# T_STorM32_motor_v25E-jst.net
KiCad netlist of a schematic drawn in EAGLE
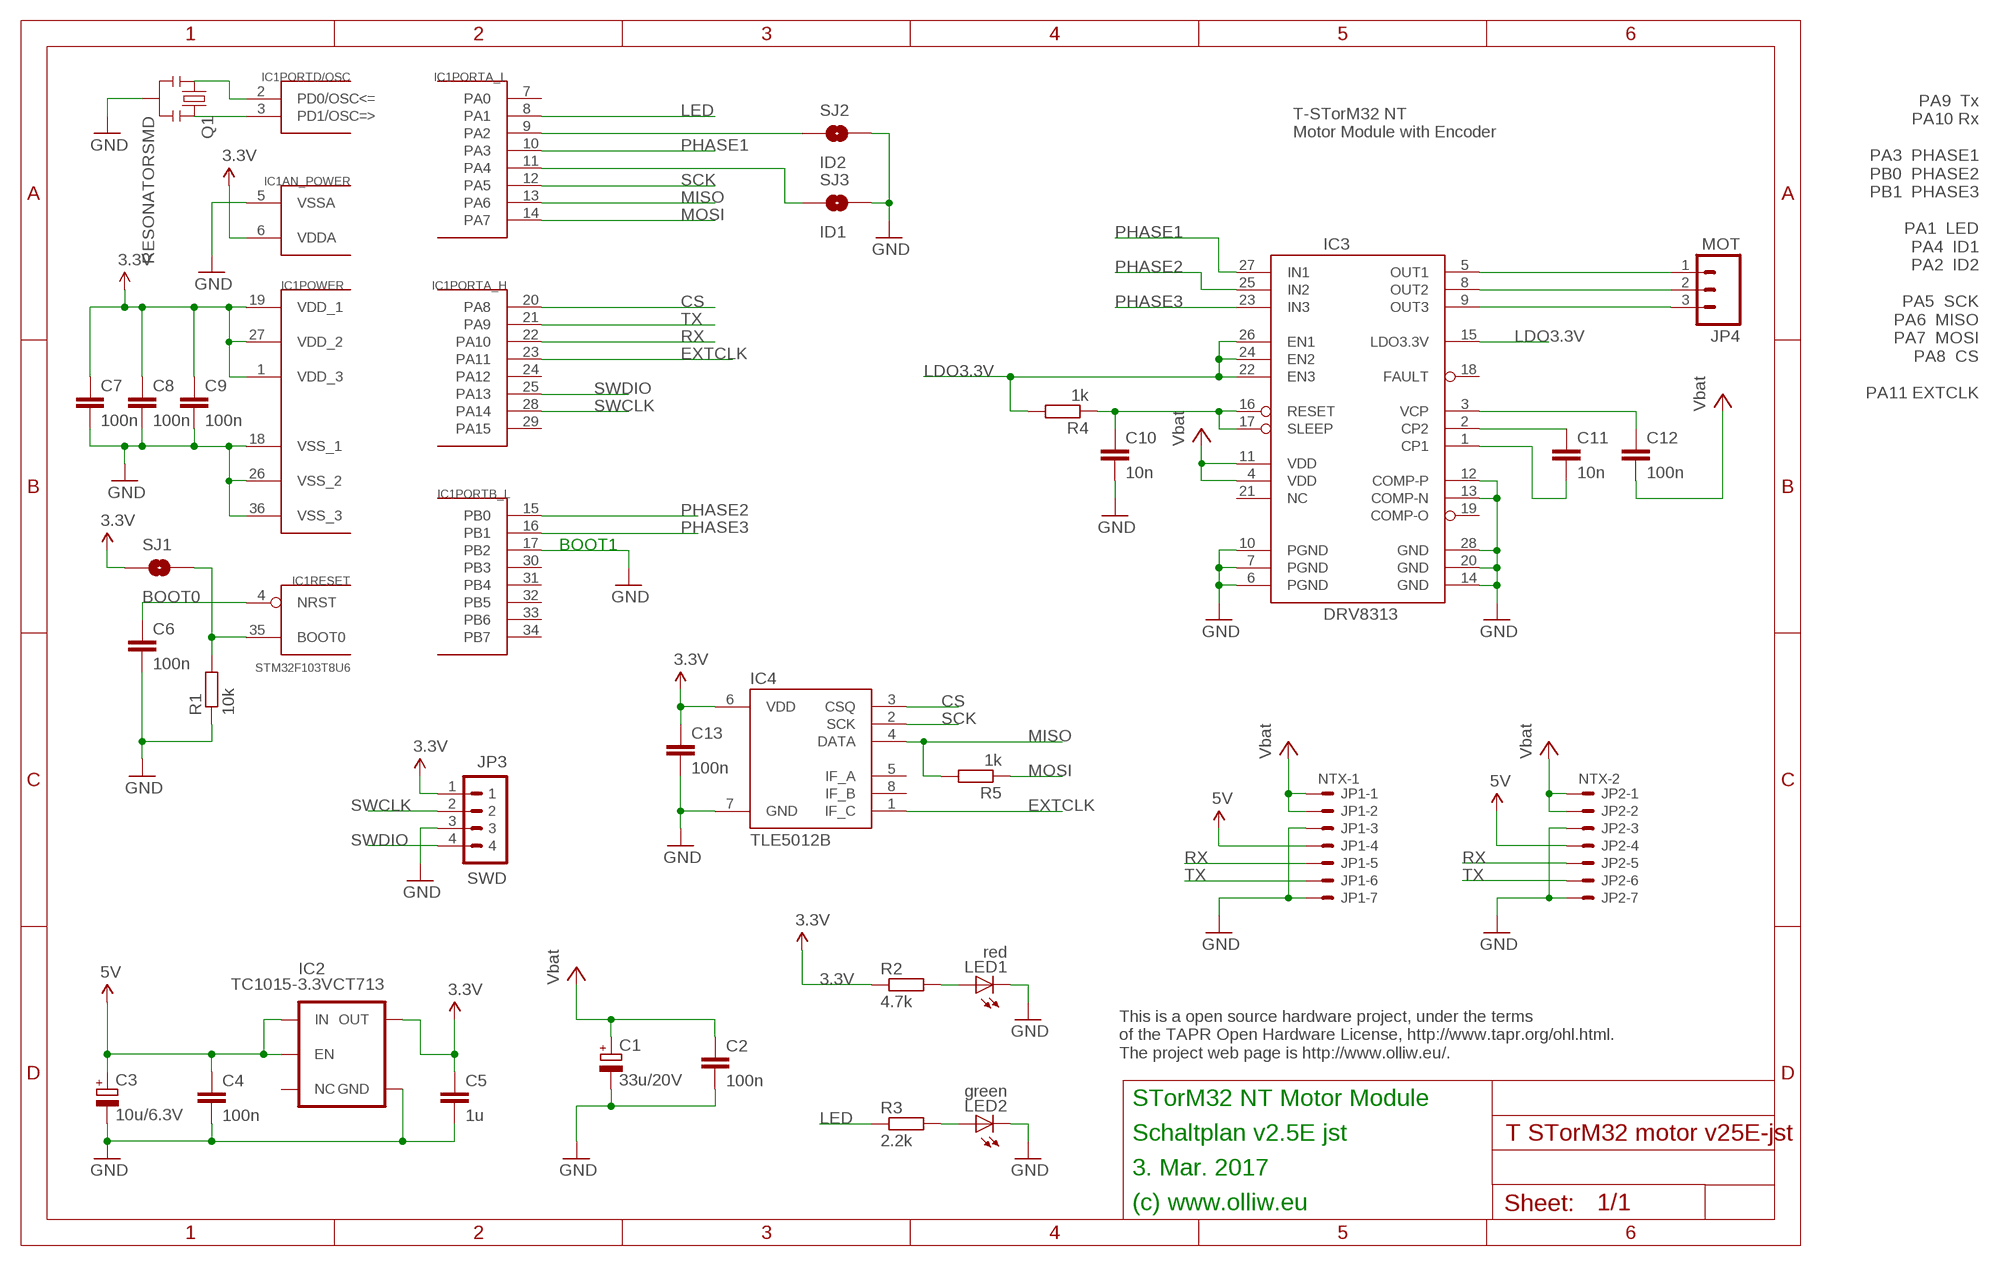
[diagram p0: schematic, sheet 1]

(export (version "E")
  (design (tool "Eeschema 10.0.6"))
  (components
    (comp (ref "C1")
      (value "33u/20V")
      (footprint "eagle-import:SMC_C")
      (libsource (lib "eagle-import") (part "CPOL-EUSMCC"))
    )
    (comp (ref "C2")
      (value "100n")
      (footprint "eagle-import:C0603")
      (libsource (lib "eagle-import") (part "C-EUC0603"))
    )
    (comp (ref "C3")
      (value "10u/6.3V")
      (footprint "eagle-import:SMC_B")
      (libsource (lib "eagle-import") (part "CPOL-EUSMCB"))
    )
    (comp (ref "C4")
      (value "100n")
      (footprint "eagle-import:C0603")
      (libsource (lib "eagle-import") (part "C-EUC0603"))
    )
    (comp (ref "C5")
      (value "1u")
      (footprint "eagle-import:C0603")
      (libsource (lib "eagle-import") (part "C-EUC0603"))
    )
    (comp (ref "C6")
      (value "100n")
      (footprint "eagle-import:C0603")
      (libsource (lib "eagle-import") (part "C-EUC0603"))
    )
    (comp (ref "C7")
      (value "100n")
      (footprint "eagle-import:C0603")
      (libsource (lib "eagle-import") (part "C-EUC0603"))
    )
    (comp (ref "C8")
      (value "100n")
      (footprint "eagle-import:C0603")
      (libsource (lib "eagle-import") (part "C-EUC0603"))
    )
    (comp (ref "C9")
      (value "100n")
      (footprint "eagle-import:C0603")
      (libsource (lib "eagle-import") (part "C-EUC0603"))
    )
    (comp (ref "C10")
      (value "10n")
      (footprint "eagle-import:C0603")
      (libsource (lib "eagle-import") (part "C-EUC0603"))
    )
    (comp (ref "C11")
      (value "10n")
      (footprint "eagle-import:C0603")
      (libsource (lib "eagle-import") (part "C-EUC0603"))
    )
    (comp (ref "C12")
      (value "100n")
      (footprint "eagle-import:C0603")
      (libsource (lib "eagle-import") (part "C-EUC0603"))
    )
    (comp (ref "C13")
      (value "100n")
      (footprint "eagle-import:C0603")
      (libsource (lib "eagle-import") (part "C-EUC0603"))
    )
    (comp (ref "IC1")
      (value "STM32F103T8U6")
      (footprint "eagle-import:VFQFPN36")
      (libsource (lib "eagle-import") (part "STM32F10XTXU6"))
    )
    (comp (ref "IC2")
      (value "TC1015-3.3VCT713")
      (footprint "eagle-import:SOT23-5")
      (libsource (lib "eagle-import") (part "V_REG_TPS76433SOT23-5"))
    )
    (comp (ref "IC3")
      (value "DRV8313")
      (footprint "eagle-import:HTSSOP28")
      (libsource (lib "eagle-import") (part "DRV8313"))
    )
    (comp (ref "IC4")
      (value "TLE5012B")
      (footprint "eagle-import:SO08")
      (libsource (lib "eagle-import") (part "TLE5012B"))
    )
    (comp (ref "JP1")
      (value "NTX-1")
      (footprint "eagle-import:SM07B-SRSS-TB")
      (libsource (lib "eagle-import") (part "?M07B-SRSS-TBS"))
    )
    (comp (ref "JP2")
      (value "NTX-2")
      (footprint "eagle-import:SM07B-SRSS-TB")
      (libsource (lib "eagle-import") (part "?M07B-SRSS-TBS"))
    )
    (comp (ref "JP3")
      (value "SWD")
      (footprint "eagle-import:4X1_1P27_OCT_BILEX")
      (libsource (lib "eagle-import") (part "P4X1_1P27-OCT_BILEX"))
    )
    (comp (ref "JP4")
      (value "MOT")
      (footprint "eagle-import:1X03")
      (libsource (lib "eagle-import") (part "M03PTH"))
    )
    (comp (ref "LED1")
      (value "red")
      (footprint "eagle-import:CHIPLED_0603")
      (libsource (lib "eagle-import") (part "LEDCHIPLED_0603"))
    )
    (comp (ref "LED2")
      (value "green")
      (footprint "eagle-import:CHIPLED_0603")
      (libsource (lib "eagle-import") (part "LEDCHIPLED_0603"))
    )
    (comp (ref "Q1")
      (value "RESONATORSMD")
      (footprint "eagle-import:RESONATOR-SMD")
      (libsource (lib "eagle-import") (part "RESONATORSMD"))
    )
    (comp (ref "R1")
      (value "10k")
      (footprint "eagle-import:R0603")
      (libsource (lib "eagle-import") (part "R-EU_R0603"))
    )
    (comp (ref "R2")
      (value "4.7k")
      (footprint "eagle-import:R0603")
      (libsource (lib "eagle-import") (part "R-EU_R0603"))
    )
    (comp (ref "R3")
      (value "2.2k")
      (footprint "eagle-import:R0603")
      (libsource (lib "eagle-import") (part "R-EU_R0603"))
    )
    (comp (ref "R4")
      (value "1k")
      (footprint "eagle-import:R0603")
      (libsource (lib "eagle-import") (part "R-EU_R0603"))
    )
    (comp (ref "R5")
      (value "1k")
      (footprint "eagle-import:R0603")
      (libsource (lib "eagle-import") (part "R-EU_R0603"))
    )
    (comp (ref "SJ1")
      (value "BOOT0")
      (footprint "eagle-import:SJ_2S-NO")
      (libsource (lib "eagle-import") (part "SOLDERJUMPERNO"))
    )
    (comp (ref "SJ2")
      (value "ID2")
      (footprint "eagle-import:SJ_2S-NO")
      (libsource (lib "eagle-import") (part "SOLDERJUMPERNO"))
    )
    (comp (ref "SJ3")
      (value "ID1")
      (footprint "eagle-import:SJ_2S-NO")
      (libsource (lib "eagle-import") (part "SOLDERJUMPERNO"))
    )
  )
  (nets
    (net (code "1") (name "/CS") (class "Default")
      (node (ref "IC1") (pin "20") (pinfunction "PA8_20") (pintype "bidirectional"))
      (node (ref "IC4") (pin "3") (pinfunction "CSQ_3") (pintype "input"))
    )
    (net (code "2") (name "/EXTCLK") (class "Default")
      (node (ref "IC1") (pin "23") (pinfunction "PA11_23") (pintype "bidirectional"))
      (node (ref "IC4") (pin "1") (pinfunction "IF_C_1") (pintype "bidirectional"))
    )
    (net (code "3") (name "/LDO3.3V") (class "Default")
      (node (ref "IC3") (pin "15") (pinfunction "LDO3.3V_15") (pintype "output"))
      (node (ref "IC3") (pin "22") (pinfunction "EN3_22") (pintype "input"))
      (node (ref "IC3") (pin "24") (pinfunction "EN2_24") (pintype "input"))
      (node (ref "IC3") (pin "26") (pinfunction "EN1_26") (pintype "input"))
      (node (ref "R4") (pin "2") (pinfunction "2_2") (pintype "passive"))
    )
    (net (code "4") (name "/LED") (class "Default")
      (node (ref "IC1") (pin "8") (pinfunction "PA1_8") (pintype "bidirectional"))
      (node (ref "R3") (pin "1") (pinfunction "1_1") (pintype "passive"))
    )
    (net (code "5") (name "/MISO") (class "Default")
      (node (ref "IC1") (pin "13") (pinfunction "PA6_13") (pintype "bidirectional"))
      (node (ref "IC4") (pin "4") (pinfunction "DATA_4") (pintype "bidirectional"))
      (node (ref "R5") (pin "2") (pinfunction "2_2") (pintype "passive"))
    )
    (net (code "6") (name "/MOSI") (class "Default")
      (node (ref "IC1") (pin "14") (pinfunction "PA7_14") (pintype "bidirectional"))
      (node (ref "R5") (pin "1") (pinfunction "1_1") (pintype "passive"))
    )
    (net (code "7") (name "/PHASE1") (class "Default")
      (node (ref "IC1") (pin "10") (pinfunction "PA3_10") (pintype "bidirectional"))
      (node (ref "IC3") (pin "27") (pinfunction "IN1_27") (pintype "input"))
    )
    (net (code "8") (name "/PHASE2") (class "Default")
      (node (ref "IC1") (pin "15") (pinfunction "PB0_15") (pintype "bidirectional"))
      (node (ref "IC3") (pin "25") (pinfunction "IN2_25") (pintype "input"))
    )
    (net (code "9") (name "/PHASE3") (class "Default")
      (node (ref "IC1") (pin "16") (pinfunction "PB1_16") (pintype "bidirectional"))
      (node (ref "IC3") (pin "23") (pinfunction "IN3_23") (pintype "input"))
    )
    (net (code "10") (name "/RX") (class "Default")
      (node (ref "IC1") (pin "22") (pinfunction "PA10_22") (pintype "bidirectional"))
      (node (ref "JP1") (pin "5") (pinfunction "S_5") (pintype "passive"))
      (node (ref "JP2") (pin "5") (pinfunction "S_5") (pintype "passive"))
    )
    (net (code "11") (name "/SCK") (class "Default")
      (node (ref "IC1") (pin "12") (pinfunction "PA5_12") (pintype "bidirectional"))
      (node (ref "IC4") (pin "2") (pinfunction "SCK_2") (pintype "input"))
    )
    (net (code "12") (name "/SWCLK") (class "Default")
      (node (ref "IC1") (pin "28") (pinfunction "PA14_28") (pintype "bidirectional"))
      (node (ref "JP3") (pin "2") (pinfunction "2_2") (pintype "passive"))
    )
    (net (code "13") (name "/SWDIO") (class "Default")
      (node (ref "IC1") (pin "25") (pinfunction "PA13_25") (pintype "bidirectional"))
      (node (ref "JP3") (pin "4") (pinfunction "4_4") (pintype "passive"))
    )
    (net (code "14") (name "/TX") (class "Default")
      (node (ref "IC1") (pin "21") (pinfunction "PA9_21") (pintype "bidirectional"))
      (node (ref "JP1") (pin "6") (pinfunction "S_6") (pintype "passive"))
      (node (ref "JP2") (pin "6") (pinfunction "S_6") (pintype "passive"))
    )
    (net (code "15") (name "3.3V") (class "Default")
      (node (ref "C13") (pin "1") (pinfunction "1_1") (pintype "passive"))
      (node (ref "C5") (pin "1") (pinfunction "1_1") (pintype "passive"))
      (node (ref "C7") (pin "1") (pinfunction "1_1") (pintype "passive"))
      (node (ref "C8") (pin "1") (pinfunction "1_1") (pintype "passive"))
      (node (ref "C9") (pin "1") (pinfunction "1_1") (pintype "passive"))
      (node (ref "IC1") (pin "1") (pinfunction "VDD_3_1") (pintype "power_in"))
      (node (ref "IC1") (pin "19") (pinfunction "VDD_1_19") (pintype "power_in"))
      (node (ref "IC1") (pin "27") (pinfunction "VDD_2_27") (pintype "power_in"))
      (node (ref "IC1") (pin "6") (pinfunction "VDDA_6") (pintype "power_in"))
      (node (ref "IC2") (pin "5") (pinfunction "OUT_5") (pintype "passive"))
      (node (ref "IC4") (pin "6") (pinfunction "VDD_6") (pintype "power_in"))
      (node (ref "JP3") (pin "1") (pinfunction "1_1") (pintype "passive"))
      (node (ref "R2") (pin "1") (pinfunction "1_1") (pintype "passive"))
      (node (ref "SJ1") (pin "1") (pinfunction "1_1") (pintype "passive"))
    )
    (net (code "16") (name "5V") (class "Default")
      (node (ref "C3") (pin "+") (pinfunction "+_+") (pintype "passive"))
      (node (ref "C4") (pin "1") (pinfunction "1_1") (pintype "passive"))
      (node (ref "IC2") (pin "1") (pinfunction "IN_1") (pintype "input"))
      (node (ref "IC2") (pin "3") (pinfunction "EN_3") (pintype "input"))
      (node (ref "JP1") (pin "4") (pinfunction "S_4") (pintype "passive"))
      (node (ref "JP2") (pin "4") (pinfunction "S_4") (pintype "passive"))
    )
    (net (code "17") (name "GND") (class "Default")
      (node (ref "C1") (pin "-") (pinfunction "-_-") (pintype "passive"))
      (node (ref "C10") (pin "2") (pinfunction "2_2") (pintype "passive"))
      (node (ref "C13") (pin "2") (pinfunction "2_2") (pintype "passive"))
      (node (ref "C2") (pin "2") (pinfunction "2_2") (pintype "passive"))
      (node (ref "C3") (pin "-") (pinfunction "-_-") (pintype "passive"))
      (node (ref "C4") (pin "2") (pinfunction "2_2") (pintype "passive"))
      (node (ref "C5") (pin "2") (pinfunction "2_2") (pintype "passive"))
      (node (ref "C6") (pin "2") (pinfunction "2_2") (pintype "passive"))
      (node (ref "C7") (pin "2") (pinfunction "2_2") (pintype "passive"))
      (node (ref "C8") (pin "2") (pinfunction "2_2") (pintype "passive"))
      (node (ref "C9") (pin "2") (pinfunction "2_2") (pintype "passive"))
      (node (ref "IC1") (pin "17") (pinfunction "PB2_17") (pintype "bidirectional"))
      (node (ref "IC1") (pin "18") (pinfunction "VSS_1_18") (pintype "power_in"))
      (node (ref "IC1") (pin "26") (pinfunction "VSS_2_26") (pintype "power_in"))
      (node (ref "IC1") (pin "36") (pinfunction "VSS_3_36") (pintype "power_in"))
      (node (ref "IC1") (pin "5") (pinfunction "VSSA_5") (pintype "power_in"))
      (node (ref "IC2") (pin "2") (pinfunction "GND_2") (pintype "input"))
      (node (ref "IC3") (pin "10") (pinfunction "PGND_10") (pintype "power_in"))
      (node (ref "IC3") (pin "12") (pinfunction "COMP-P_12") (pintype "input"))
      (node (ref "IC3") (pin "13") (pinfunction "COMP-N_13") (pintype "input"))
      (node (ref "IC3") (pin "14") (pinfunction "GND_14") (pintype "power_in"))
      (node (ref "IC3") (pin "20") (pinfunction "GND_20") (pintype "power_in"))
      (node (ref "IC3") (pin "28") (pinfunction "GND_28") (pintype "power_in"))
      (node (ref "IC3") (pin "6") (pinfunction "PGND_6") (pintype "power_in"))
      (node (ref "IC3") (pin "7") (pinfunction "PGND_7") (pintype "power_in"))
      (node (ref "IC4") (pin "7") (pinfunction "GND_7") (pintype "power_in"))
      (node (ref "JP1") (pin "3") (pinfunction "S_3") (pintype "passive"))
      (node (ref "JP1") (pin "7") (pinfunction "S_7") (pintype "passive"))
      (node (ref "JP2") (pin "3") (pinfunction "S_3") (pintype "passive"))
      (node (ref "JP2") (pin "7") (pinfunction "S_7") (pintype "passive"))
      (node (ref "JP3") (pin "3") (pinfunction "3_3") (pintype "passive"))
      (node (ref "LED1") (pin "C") (pinfunction "C_C") (pintype "passive"))
      (node (ref "LED2") (pin "C") (pinfunction "C_C") (pintype "passive"))
      (node (ref "Q1") (pin "2") (pinfunction "2_2") (pintype "passive"))
      (node (ref "R1") (pin "1") (pinfunction "1_1") (pintype "passive"))
      (node (ref "SJ2") (pin "2") (pinfunction "2_2") (pintype "passive"))
      (node (ref "SJ3") (pin "2") (pinfunction "2_2") (pintype "passive"))
    )
    (net (code "18") (name "Net-(IC1C-PA2)") (class "Default")
      (node (ref "IC1") (pin "9") (pinfunction "PA2_9") (pintype "bidirectional"))
      (node (ref "SJ2") (pin "1") (pinfunction "1_1") (pintype "passive"))
    )
    (net (code "19") (name "Net-(IC1C-PA4)") (class "Default")
      (node (ref "IC1") (pin "11") (pinfunction "PA4_11") (pintype "bidirectional"))
      (node (ref "SJ3") (pin "1") (pinfunction "1_1") (pintype "passive"))
    )
    (net (code "20") (name "Net-(IC1E-PD0{slash}OSC<=)") (class "Default")
      (node (ref "IC1") (pin "2") (pinfunction "PD0/OSC<=_2") (pintype "bidirectional"))
      (node (ref "Q1") (pin "1") (pinfunction "1_1") (pintype "passive"))
    )
    (net (code "21") (name "Net-(IC1E-PD1{slash}OSC=>)") (class "Default")
      (node (ref "IC1") (pin "3") (pinfunction "PD1/OSC=>_3") (pintype "bidirectional"))
      (node (ref "Q1") (pin "3") (pinfunction "3_3") (pintype "passive"))
    )
    (net (code "22") (name "Net-(IC1G-BOOT0)") (class "Default")
      (node (ref "IC1") (pin "35") (pinfunction "BOOT0_35") (pintype "input"))
      (node (ref "R1") (pin "2") (pinfunction "2_2") (pintype "passive"))
      (node (ref "SJ1") (pin "2") (pinfunction "2_2") (pintype "passive"))
    )
    (net (code "23") (name "Net-(IC1G-NRST)") (class "Default")
      (node (ref "C6") (pin "1") (pinfunction "1_1") (pintype "passive"))
      (node (ref "IC1") (pin "4") (pinfunction "NRST_4") (pintype "input"))
    )
    (net (code "24") (name "Net-(IC3-CP1)") (class "Default")
      (node (ref "C11") (pin "2") (pinfunction "2_2") (pintype "passive"))
      (node (ref "IC3") (pin "1") (pinfunction "CP1_1") (pintype "bidirectional"))
    )
    (net (code "25") (name "Net-(IC3-CP2)") (class "Default")
      (node (ref "C11") (pin "1") (pinfunction "1_1") (pintype "passive"))
      (node (ref "IC3") (pin "2") (pinfunction "CP2_2") (pintype "bidirectional"))
    )
    (net (code "26") (name "Net-(IC3-OUT1)") (class "Default")
      (node (ref "IC3") (pin "5") (pinfunction "OUT1_5") (pintype "output"))
      (node (ref "JP4") (pin "1") (pinfunction "1_1") (pintype "passive"))
    )
    (net (code "27") (name "Net-(IC3-OUT2)") (class "Default")
      (node (ref "IC3") (pin "8") (pinfunction "OUT2_8") (pintype "output"))
      (node (ref "JP4") (pin "2") (pinfunction "2_2") (pintype "passive"))
    )
    (net (code "28") (name "Net-(IC3-OUT3)") (class "Default")
      (node (ref "IC3") (pin "9") (pinfunction "OUT3_9") (pintype "output"))
      (node (ref "JP4") (pin "3") (pinfunction "3_3") (pintype "passive"))
    )
    (net (code "29") (name "Net-(IC3-RESET)") (class "Default")
      (node (ref "C10") (pin "1") (pinfunction "1_1") (pintype "passive"))
      (node (ref "IC3") (pin "16") (pinfunction "RESET_16") (pintype "input"))
      (node (ref "IC3") (pin "17") (pinfunction "SLEEP_17") (pintype "input"))
      (node (ref "R4") (pin "1") (pinfunction "1_1") (pintype "passive"))
    )
    (net (code "30") (name "Net-(IC3-VCP)") (class "Default")
      (node (ref "C12") (pin "1") (pinfunction "1_1") (pintype "passive"))
      (node (ref "IC3") (pin "3") (pinfunction "VCP_3") (pintype "bidirectional"))
    )
    (net (code "31") (name "Net-(LED1-PadA)") (class "Default")
      (node (ref "LED1") (pin "A") (pinfunction "A_A") (pintype "passive"))
      (node (ref "R2") (pin "2") (pinfunction "2_2") (pintype "passive"))
    )
    (net (code "32") (name "Net-(LED2-PadA)") (class "Default")
      (node (ref "LED2") (pin "A") (pinfunction "A_A") (pintype "passive"))
      (node (ref "R3") (pin "2") (pinfunction "2_2") (pintype "passive"))
    )
    (net (code "33") (name "Vbat") (class "Default")
      (node (ref "C1") (pin "+") (pinfunction "+_+") (pintype "passive"))
      (node (ref "C12") (pin "2") (pinfunction "2_2") (pintype "passive"))
      (node (ref "C2") (pin "1") (pinfunction "1_1") (pintype "passive"))
      (node (ref "IC3") (pin "11") (pinfunction "VDD_11") (pintype "power_in"))
      (node (ref "IC3") (pin "4") (pinfunction "VDD_4") (pintype "power_in"))
      (node (ref "JP1") (pin "1") (pinfunction "S_1") (pintype "passive"))
      (node (ref "JP1") (pin "2") (pinfunction "S_2") (pintype "passive"))
      (node (ref "JP2") (pin "1") (pinfunction "S_1") (pintype "passive"))
      (node (ref "JP2") (pin "2") (pinfunction "S_2") (pintype "passive"))
    )
    (net (code "34") (name "unconnected-(IC1B-PA12-Pad24)") (class "Default")
      (node (ref "IC1") (pin "24") (pinfunction "PA12_24") (pintype "bidirectional"))
    )
    (net (code "35") (name "unconnected-(IC1B-PA15-Pad29)") (class "Default")
      (node (ref "IC1") (pin "29") (pinfunction "PA15_29") (pintype "bidirectional"))
    )
    (net (code "36") (name "unconnected-(IC1C-PA0-Pad7)") (class "Default")
      (node (ref "IC1") (pin "7") (pinfunction "PA0_7") (pintype "bidirectional"))
    )
    (net (code "37") (name "unconnected-(IC1D-PB3-Pad30)") (class "Default")
      (node (ref "IC1") (pin "30") (pinfunction "PB3_30") (pintype "bidirectional"))
    )
    (net (code "38") (name "unconnected-(IC1D-PB4-Pad31)") (class "Default")
      (node (ref "IC1") (pin "31") (pinfunction "PB4_31") (pintype "bidirectional"))
    )
    (net (code "39") (name "unconnected-(IC1D-PB5-Pad32)") (class "Default")
      (node (ref "IC1") (pin "32") (pinfunction "PB5_32") (pintype "bidirectional"))
    )
    (net (code "40") (name "unconnected-(IC1D-PB6-Pad33)") (class "Default")
      (node (ref "IC1") (pin "33") (pinfunction "PB6_33") (pintype "bidirectional"))
    )
    (net (code "41") (name "unconnected-(IC1D-PB7-Pad34)") (class "Default")
      (node (ref "IC1") (pin "34") (pinfunction "PB7_34") (pintype "bidirectional"))
    )
    (net (code "42") (name "unconnected-(IC2-NC-Pad4)") (class "Default")
      (node (ref "IC2") (pin "4") (pinfunction "NC_4") (pintype "input"))
    )
    (net (code "43") (name "unconnected-(IC3-COMP-O-Pad19)") (class "Default")
      (node (ref "IC3") (pin "19") (pinfunction "COMP-O_19") (pintype "output"))
    )
    (net (code "44") (name "unconnected-(IC3-FAULT-Pad18)") (class "Default")
      (node (ref "IC3") (pin "18") (pinfunction "FAULT_18") (pintype "output"))
    )
    (net (code "45") (name "unconnected-(IC3-NC-Pad21)") (class "Default")
      (node (ref "IC3") (pin "21") (pinfunction "NC_21") (pintype "no_connect"))
    )
    (net (code "46") (name "unconnected-(IC4-IF_A-Pad5)") (class "Default")
      (node (ref "IC4") (pin "5") (pinfunction "IF_A_5") (pintype "bidirectional"))
    )
    (net (code "47") (name "unconnected-(IC4-IF_B-Pad8)") (class "Default")
      (node (ref "IC4") (pin "8") (pinfunction "IF_B_8") (pintype "output"))
    )
  )
)
